# sumo_motor_5.net
KiCad netlist of a schematic drawn in EAGLE
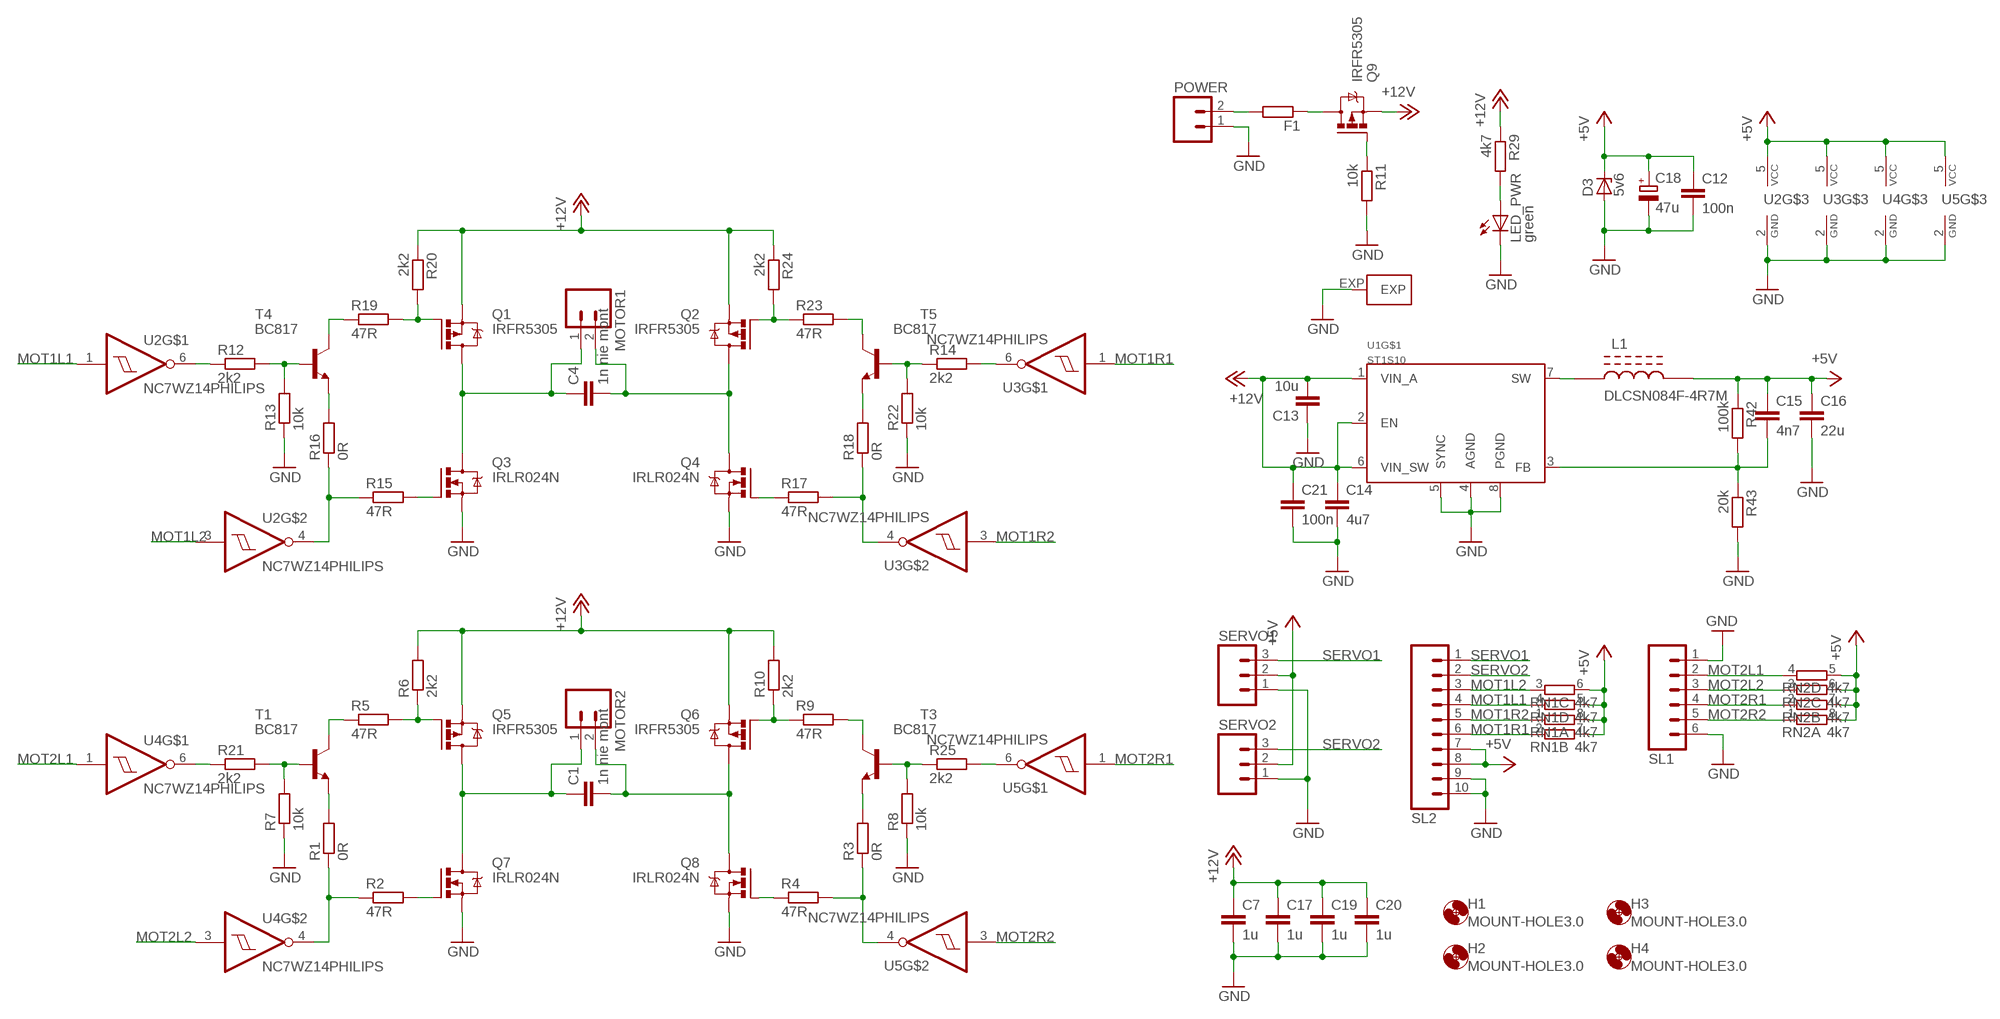
[diagram p0: schematic, sheet 1]

(export (version "E")
  (design (tool "Eeschema 10.0.6"))
  (components
    (comp (ref "C1")
      (value "1n nie mont")
      (footprint "eagle-import:C025-025X050")
      (libsource (lib "eagle-import") (part "C-EU025-025X050"))
    )
    (comp (ref "C4")
      (value "1n nie mont")
      (footprint "eagle-import:C025-025X050")
      (libsource (lib "eagle-import") (part "C-EU025-025X050"))
    )
    (comp (ref "C7")
      (value "1u")
      (footprint "eagle-import:C0805")
      (libsource (lib "eagle-import") (part "C-EUC0805"))
    )
    (comp (ref "C12")
      (value "100n")
      (footprint "eagle-import:C0805")
      (libsource (lib "eagle-import") (part "C-EUC0805"))
    )
    (comp (ref "C13")
      (value "10u")
      (footprint "eagle-import:C1206K")
      (libsource (lib "eagle-import") (part "C-EUC1206K"))
    )
    (comp (ref "C14")
      (value "4u7")
      (footprint "eagle-import:C0805")
      (libsource (lib "eagle-import") (part "C-EUC0805"))
    )
    (comp (ref "C15")
      (value "4n7")
      (footprint "eagle-import:C0805")
      (libsource (lib "eagle-import") (part "C-EUC0805"))
    )
    (comp (ref "C16")
      (value "22u")
      (footprint "eagle-import:C0805")
      (libsource (lib "eagle-import") (part "C-EUC0805"))
    )
    (comp (ref "C17")
      (value "1u")
      (footprint "eagle-import:C0805")
      (libsource (lib "eagle-import") (part "C-EUC0805"))
    )
    (comp (ref "C18")
      (value "47u")
      (footprint "eagle-import:SMC_B")
      (libsource (lib "eagle-import") (part "CPOL-EUSMCB"))
    )
    (comp (ref "C19")
      (value "1u")
      (footprint "eagle-import:C0805")
      (libsource (lib "eagle-import") (part "C-EUC0805"))
    )
    (comp (ref "C20")
      (value "1u")
      (footprint "eagle-import:C0805")
      (libsource (lib "eagle-import") (part "C-EUC0805"))
    )
    (comp (ref "C21")
      (value "100n")
      (footprint "eagle-import:C0805")
      (libsource (lib "eagle-import") (part "C-EUC0805"))
    )
    (comp (ref "D3")
      (value "5v6")
      (footprint "eagle-import:SMB")
      (libsource (lib "eagle-import") (part "ZENER-DIODESMB"))
    )
    (comp (ref "F1")
      (value "R-EU_VMTA55")
      (footprint "eagle-import:VMTA55")
      (libsource (lib "eagle-import") (part "R-EU_VMTA55"))
    )
    (comp (ref "H1")
      (value "MOUNT-HOLE3.0")
      (footprint "eagle-import:3,0")
      (libsource (lib "eagle-import") (part "MOUNT-HOLE3.0"))
    )
    (comp (ref "H2")
      (value "MOUNT-HOLE3.0")
      (footprint "eagle-import:3,0")
      (libsource (lib "eagle-import") (part "MOUNT-HOLE3.0"))
    )
    (comp (ref "H3")
      (value "MOUNT-HOLE3.0")
      (footprint "eagle-import:3,0")
      (libsource (lib "eagle-import") (part "MOUNT-HOLE3.0"))
    )
    (comp (ref "H4")
      (value "MOUNT-HOLE3.0")
      (footprint "eagle-import:3,0")
      (libsource (lib "eagle-import") (part "MOUNT-HOLE3.0"))
    )
    (comp (ref "L1")
      (value "DLCSN084F-4R7M")
      (footprint "eagle-import:CSN084F")
      (libsource (lib "eagle-import") (part "DLCSN084F"))
    )
    (comp (ref "LED_PWR")
      (value "green")
      (footprint "eagle-import:SML0805")
      (libsource (lib "eagle-import") (part "LEDSML0805"))
    )
    (comp (ref "MOTOR1")
      (value "M02")
      (footprint "eagle-import:02P")
      (libsource (lib "eagle-import") (part "M02"))
    )
    (comp (ref "MOTOR2")
      (value "M02")
      (footprint "eagle-import:02P")
      (libsource (lib "eagle-import") (part "M02"))
    )
    (comp (ref "POWER")
      (value "M02")
      (footprint "eagle-import:02P")
      (libsource (lib "eagle-import") (part "M02"))
    )
    (comp (ref "Q1")
      (value "IRFR5305")
      (footprint "eagle-import:D-PAK_TO252AA")
      (libsource (lib "eagle-import") (part "IRF?5305R"))
    )
    (comp (ref "Q2")
      (value "IRFR5305")
      (footprint "eagle-import:D-PAK_TO252AA")
      (libsource (lib "eagle-import") (part "IRF?5305R"))
    )
    (comp (ref "Q3")
      (value "IRLR024N")
      (footprint "eagle-import:D-PAK_TO252AA")
      (libsource (lib "eagle-import") (part "IRLR024N"))
    )
    (comp (ref "Q4")
      (value "IRLR024N")
      (footprint "eagle-import:D-PAK_TO252AA")
      (libsource (lib "eagle-import") (part "IRLR024N"))
    )
    (comp (ref "Q5")
      (value "IRFR5305")
      (footprint "eagle-import:D-PAK_TO252AA")
      (libsource (lib "eagle-import") (part "IRF?5305R"))
    )
    (comp (ref "Q6")
      (value "IRFR5305")
      (footprint "eagle-import:D-PAK_TO252AA")
      (libsource (lib "eagle-import") (part "IRF?5305R"))
    )
    (comp (ref "Q7")
      (value "IRLR024N")
      (footprint "eagle-import:D-PAK_TO252AA")
      (libsource (lib "eagle-import") (part "IRLR024N"))
    )
    (comp (ref "Q8")
      (value "IRLR024N")
      (footprint "eagle-import:D-PAK_TO252AA")
      (libsource (lib "eagle-import") (part "IRLR024N"))
    )
    (comp (ref "Q9")
      (value "IRFR5305")
      (footprint "eagle-import:D-PAK_TO252AA")
      (libsource (lib "eagle-import") (part "IRF?5305R"))
    )
    (comp (ref "R1")
      (value "0R")
      (footprint "eagle-import:R0603")
      (libsource (lib "eagle-import") (part "R-EU_R0603"))
    )
    (comp (ref "R2")
      (value "47R")
      (footprint "eagle-import:R0603")
      (libsource (lib "eagle-import") (part "R-EU_R0603"))
    )
    (comp (ref "R3")
      (value "0R")
      (footprint "eagle-import:R0603")
      (libsource (lib "eagle-import") (part "R-EU_R0603"))
    )
    (comp (ref "R4")
      (value "47R")
      (footprint "eagle-import:R0603")
      (libsource (lib "eagle-import") (part "R-EU_R0603"))
    )
    (comp (ref "R5")
      (value "47R")
      (footprint "eagle-import:R0603")
      (libsource (lib "eagle-import") (part "R-EU_R0603"))
    )
    (comp (ref "R6")
      (value "2k2")
      (footprint "eagle-import:R0603")
      (libsource (lib "eagle-import") (part "R-EU_R0603"))
    )
    (comp (ref "R7")
      (value "10k")
      (footprint "eagle-import:R0603")
      (libsource (lib "eagle-import") (part "R-EU_R0603"))
    )
    (comp (ref "R8")
      (value "10k")
      (footprint "eagle-import:R0603")
      (libsource (lib "eagle-import") (part "R-EU_R0603"))
    )
    (comp (ref "R9")
      (value "47R")
      (footprint "eagle-import:R0603")
      (libsource (lib "eagle-import") (part "R-EU_R0603"))
    )
    (comp (ref "R10")
      (value "2k2")
      (footprint "eagle-import:R0603")
      (libsource (lib "eagle-import") (part "R-EU_R0603"))
    )
    (comp (ref "R11")
      (value "10k")
      (footprint "eagle-import:R0603")
      (libsource (lib "eagle-import") (part "R-EU_R0603"))
    )
    (comp (ref "R12")
      (value "2k2")
      (footprint "eagle-import:R0603")
      (libsource (lib "eagle-import") (part "R-EU_R0603"))
    )
    (comp (ref "R13")
      (value "10k")
      (footprint "eagle-import:R0603")
      (libsource (lib "eagle-import") (part "R-EU_R0603"))
    )
    (comp (ref "R14")
      (value "2k2")
      (footprint "eagle-import:R0603")
      (libsource (lib "eagle-import") (part "R-EU_R0603"))
    )
    (comp (ref "R15")
      (value "47R")
      (footprint "eagle-import:R0603")
      (libsource (lib "eagle-import") (part "R-EU_R0603"))
    )
    (comp (ref "R16")
      (value "0R")
      (footprint "eagle-import:R0603")
      (libsource (lib "eagle-import") (part "R-EU_R0603"))
    )
    (comp (ref "R17")
      (value "47R")
      (footprint "eagle-import:R0603")
      (libsource (lib "eagle-import") (part "R-EU_R0603"))
    )
    (comp (ref "R18")
      (value "0R")
      (footprint "eagle-import:R0603")
      (libsource (lib "eagle-import") (part "R-EU_R0603"))
    )
    (comp (ref "R19")
      (value "47R")
      (footprint "eagle-import:R0603")
      (libsource (lib "eagle-import") (part "R-EU_R0603"))
    )
    (comp (ref "R20")
      (value "2k2")
      (footprint "eagle-import:R0603")
      (libsource (lib "eagle-import") (part "R-EU_R0603"))
    )
    (comp (ref "R21")
      (value "2k2")
      (footprint "eagle-import:R0603")
      (libsource (lib "eagle-import") (part "R-EU_R0603"))
    )
    (comp (ref "R22")
      (value "10k")
      (footprint "eagle-import:R0603")
      (libsource (lib "eagle-import") (part "R-EU_R0603"))
    )
    (comp (ref "R23")
      (value "47R")
      (footprint "eagle-import:R0603")
      (libsource (lib "eagle-import") (part "R-EU_R0603"))
    )
    (comp (ref "R24")
      (value "2k2")
      (footprint "eagle-import:R0603")
      (libsource (lib "eagle-import") (part "R-EU_R0603"))
    )
    (comp (ref "R25")
      (value "2k2")
      (footprint "eagle-import:R0603")
      (libsource (lib "eagle-import") (part "R-EU_R0603"))
    )
    (comp (ref "R29")
      (value "4k7")
      (footprint "eagle-import:R0603")
      (libsource (lib "eagle-import") (part "R-EU_R0603"))
    )
    (comp (ref "R42")
      (value "100k")
      (footprint "eagle-import:R0603")
      (libsource (lib "eagle-import") (part "R-EU_R0603"))
    )
    (comp (ref "R43")
      (value "20k")
      (footprint "eagle-import:R0603")
      (libsource (lib "eagle-import") (part "R-EU_R0603"))
    )
    (comp (ref "RN1")
      (value "4k7")
      (footprint "eagle-import:CAT16XXX")
      (libsource (lib "eagle-import") (part "CAT16XXXJ4CAT16"))
    )
    (comp (ref "RN2")
      (value "4k7")
      (footprint "eagle-import:CAT16XXX")
      (libsource (lib "eagle-import") (part "CAT16XXXJ4CAT16"))
    )
    (comp (ref "SERVO1")
      (value "M03")
      (footprint "eagle-import:03P")
      (libsource (lib "eagle-import") (part "M03"))
    )
    (comp (ref "SERVO2")
      (value "M03")
      (footprint "eagle-import:03P")
      (libsource (lib "eagle-import") (part "M03"))
    )
    (comp (ref "SL1")
      (value "M06")
      (footprint "eagle-import:06P")
      (fields (field (name "OC_FARNELL") "unknown") (field (name "OC_NEWARK") "unknown"))
      (libsource (lib "eagle-import") (part "M06"))
    )
    (comp (ref "SL2")
      (value "M10")
      (footprint "eagle-import:10P")
      (fields (field (name "OC_FARNELL") "unknown") (field (name "OC_NEWARK") "unknown"))
      (libsource (lib "eagle-import") (part "M10"))
    )
    (comp (ref "T1")
      (value "BC817")
      (footprint "eagle-import:SOT23-BEC")
      (libsource (lib "eagle-import") (part "-NPN-SOT23-BECBC817-16"))
    )
    (comp (ref "T3")
      (value "BC817")
      (footprint "eagle-import:SOT23-BEC")
      (libsource (lib "eagle-import") (part "-NPN-SOT23-BECBC817-16"))
    )
    (comp (ref "T4")
      (value "BC817")
      (footprint "eagle-import:SOT23-BEC")
      (libsource (lib "eagle-import") (part "-NPN-SOT23-BECBC817-16"))
    )
    (comp (ref "T5")
      (value "BC817")
      (footprint "eagle-import:SOT23-BEC")
      (libsource (lib "eagle-import") (part "-NPN-SOT23-BECBC817-16"))
    )
    (comp (ref "U1")
      (value "ST1S10")
      (footprint "eagle-import:HSOP8")
      (libsource (lib "eagle-import") (part "ST1S10"))
    )
    (comp (ref "U2")
      (value "NC7WZ14PHILIPS")
      (footprint "eagle-import:SOT363_PHILIPS")
      (libsource (lib "eagle-import") (part "NC7WZ14PHILIPS"))
    )
    (comp (ref "U3")
      (value "NC7WZ14PHILIPS")
      (footprint "eagle-import:SOT363_PHILIPS")
      (libsource (lib "eagle-import") (part "NC7WZ14PHILIPS"))
    )
    (comp (ref "U4")
      (value "NC7WZ14PHILIPS")
      (footprint "eagle-import:SOT363_PHILIPS")
      (libsource (lib "eagle-import") (part "NC7WZ14PHILIPS"))
    )
    (comp (ref "U5")
      (value "NC7WZ14PHILIPS")
      (footprint "eagle-import:SOT363_PHILIPS")
      (libsource (lib "eagle-import") (part "NC7WZ14PHILIPS"))
    )
  )
  (nets
    (net (code "1") (name "+5V") (class "Default")
      (node (ref "C12") (pin "1") (pinfunction "1_1") (pintype "passive"))
      (node (ref "C15") (pin "1") (pinfunction "1_1") (pintype "passive"))
      (node (ref "C16") (pin "1") (pinfunction "1_1") (pintype "passive"))
      (node (ref "C18") (pin "+") (pinfunction "+_+") (pintype "passive"))
      (node (ref "D3") (pin "C") (pinfunction "C_C") (pintype "passive"))
      (node (ref "L1") (pin "2") (pinfunction "2_2") (pintype "passive"))
      (node (ref "R42") (pin "1") (pinfunction "1_1") (pintype "passive"))
      (node (ref "RN1") (pin "5") (pinfunction "2_5") (pintype "passive"))
      (node (ref "RN1") (pin "6") (pinfunction "2_6") (pintype "passive"))
      (node (ref "RN1") (pin "7") (pinfunction "2_7") (pintype "passive"))
      (node (ref "RN1") (pin "8") (pinfunction "2_8") (pintype "passive"))
      (node (ref "RN2") (pin "5") (pinfunction "2_5") (pintype "passive"))
      (node (ref "RN2") (pin "6") (pinfunction "2_6") (pintype "passive"))
      (node (ref "RN2") (pin "7") (pinfunction "2_7") (pintype "passive"))
      (node (ref "RN2") (pin "8") (pinfunction "2_8") (pintype "passive"))
      (node (ref "SERVO1") (pin "2") (pinfunction "2_2") (pintype "passive"))
      (node (ref "SERVO2") (pin "2") (pinfunction "2_2") (pintype "passive"))
      (node (ref "SL2") (pin "7") (pinfunction "7_7") (pintype "passive"))
      (node (ref "SL2") (pin "8") (pinfunction "8_8") (pintype "passive"))
      (node (ref "U2") (pin "5") (pinfunction "VCC_5") (pintype "power_in"))
      (node (ref "U3") (pin "5") (pinfunction "VCC_5") (pintype "power_in"))
      (node (ref "U4") (pin "5") (pinfunction "VCC_5") (pintype "power_in"))
      (node (ref "U5") (pin "5") (pinfunction "VCC_5") (pintype "power_in"))
    )
    (net (code "2") (name "+12V") (class "Default")
      (node (ref "C13") (pin "2") (pinfunction "2_2") (pintype "passive"))
      (node (ref "C14") (pin "1") (pinfunction "1_1") (pintype "passive"))
      (node (ref "C17") (pin "1") (pinfunction "1_1") (pintype "passive"))
      (node (ref "C19") (pin "1") (pinfunction "1_1") (pintype "passive"))
      (node (ref "C20") (pin "1") (pinfunction "1_1") (pintype "passive"))
      (node (ref "C21") (pin "1") (pinfunction "1_1") (pintype "passive"))
      (node (ref "C7") (pin "1") (pinfunction "1_1") (pintype "passive"))
      (node (ref "Q1") (pin "3") (pinfunction "S_3") (pintype "passive"))
      (node (ref "Q2") (pin "3") (pinfunction "S_3") (pintype "passive"))
      (node (ref "Q5") (pin "3") (pinfunction "S_3") (pintype "passive"))
      (node (ref "Q6") (pin "3") (pinfunction "S_3") (pintype "passive"))
      (node (ref "Q9") (pin "3") (pinfunction "S_3") (pintype "passive"))
      (node (ref "R10") (pin "2") (pinfunction "2_2") (pintype "passive"))
      (node (ref "R20") (pin "1") (pinfunction "1_1") (pintype "passive"))
      (node (ref "R24") (pin "1") (pinfunction "1_1") (pintype "passive"))
      (node (ref "R29") (pin "1") (pinfunction "1_1") (pintype "passive"))
      (node (ref "R6") (pin "2") (pinfunction "2_2") (pintype "passive"))
      (node (ref "U1") (pin "1") (pinfunction "VIN_A_1") (pintype "power_in"))
      (node (ref "U1") (pin "2") (pinfunction "EN_2") (pintype "bidirectional"))
      (node (ref "U1") (pin "6") (pinfunction "VIN_SW_6") (pintype "power_in"))
    )
    (net (code "3") (name "/MOT1L1") (class "Default")
      (node (ref "RN1") (pin "4") (pinfunction "1_4") (pintype "passive"))
      (node (ref "SL2") (pin "4") (pinfunction "4_4") (pintype "passive"))
      (node (ref "U2") (pin "1") (pinfunction "I_1") (pintype "input"))
    )
    (net (code "4") (name "/MOT1L2") (class "Default")
      (node (ref "RN1") (pin "3") (pinfunction "1_3") (pintype "passive"))
      (node (ref "SL2") (pin "3") (pinfunction "3_3") (pintype "passive"))
      (node (ref "U2") (pin "3") (pinfunction "I_3") (pintype "input"))
    )
    (net (code "5") (name "/MOT1R1") (class "Default")
      (node (ref "RN1") (pin "2") (pinfunction "1_2") (pintype "passive"))
      (node (ref "SL2") (pin "6") (pinfunction "6_6") (pintype "passive"))
      (node (ref "U3") (pin "1") (pinfunction "I_1") (pintype "input"))
    )
    (net (code "6") (name "/MOT1R2") (class "Default")
      (node (ref "RN1") (pin "1") (pinfunction "1_1") (pintype "passive"))
      (node (ref "SL2") (pin "5") (pinfunction "5_5") (pintype "passive"))
      (node (ref "U3") (pin "3") (pinfunction "I_3") (pintype "input"))
    )
    (net (code "7") (name "/MOT2L1") (class "Default")
      (node (ref "RN2") (pin "4") (pinfunction "1_4") (pintype "passive"))
      (node (ref "SL1") (pin "2") (pinfunction "2_2") (pintype "passive"))
      (node (ref "U4") (pin "1") (pinfunction "I_1") (pintype "input"))
    )
    (net (code "8") (name "/MOT2L2") (class "Default")
      (node (ref "RN2") (pin "3") (pinfunction "1_3") (pintype "passive"))
      (node (ref "SL1") (pin "3") (pinfunction "3_3") (pintype "passive"))
      (node (ref "U4") (pin "3") (pinfunction "I_3") (pintype "input"))
    )
    (net (code "9") (name "/MOT2R1") (class "Default")
      (node (ref "RN2") (pin "2") (pinfunction "1_2") (pintype "passive"))
      (node (ref "SL1") (pin "4") (pinfunction "4_4") (pintype "passive"))
      (node (ref "U5") (pin "1") (pinfunction "I_1") (pintype "input"))
    )
    (net (code "10") (name "/MOT2R2") (class "Default")
      (node (ref "RN2") (pin "1") (pinfunction "1_1") (pintype "passive"))
      (node (ref "SL1") (pin "5") (pinfunction "5_5") (pintype "passive"))
      (node (ref "U5") (pin "3") (pinfunction "I_3") (pintype "input"))
    )
    (net (code "11") (name "/SERVO1") (class "Default")
      (node (ref "SERVO1") (pin "3") (pinfunction "3_3") (pintype "passive"))
      (node (ref "SL2") (pin "1") (pinfunction "1_1") (pintype "passive"))
    )
    (net (code "12") (name "/SERVO2") (class "Default")
      (node (ref "SERVO2") (pin "3") (pinfunction "3_3") (pintype "passive"))
      (node (ref "SL2") (pin "2") (pinfunction "2_2") (pintype "passive"))
    )
    (net (code "13") (name "GND") (class "Default")
      (node (ref "C12") (pin "2") (pinfunction "2_2") (pintype "passive"))
      (node (ref "C13") (pin "1") (pinfunction "1_1") (pintype "passive"))
      (node (ref "C14") (pin "2") (pinfunction "2_2") (pintype "passive"))
      (node (ref "C16") (pin "2") (pinfunction "2_2") (pintype "passive"))
      (node (ref "C17") (pin "2") (pinfunction "2_2") (pintype "passive"))
      (node (ref "C18") (pin "-") (pinfunction "-_-") (pintype "passive"))
      (node (ref "C19") (pin "2") (pinfunction "2_2") (pintype "passive"))
      (node (ref "C20") (pin "2") (pinfunction "2_2") (pintype "passive"))
      (node (ref "C21") (pin "2") (pinfunction "2_2") (pintype "passive"))
      (node (ref "C7") (pin "2") (pinfunction "2_2") (pintype "passive"))
      (node (ref "D3") (pin "A") (pinfunction "A_A") (pintype "passive"))
      (node (ref "LED_PWR") (pin "C") (pinfunction "C_C") (pintype "passive"))
      (node (ref "POWER") (pin "1") (pinfunction "1_1") (pintype "passive"))
      (node (ref "Q3") (pin "3") (pinfunction "S_3") (pintype "passive"))
      (node (ref "Q4") (pin "3") (pinfunction "S_3") (pintype "passive"))
      (node (ref "Q7") (pin "3") (pinfunction "S_3") (pintype "passive"))
      (node (ref "Q8") (pin "3") (pinfunction "S_3") (pintype "passive"))
      (node (ref "R11") (pin "2") (pinfunction "2_2") (pintype "passive"))
      (node (ref "R13") (pin "1") (pinfunction "1_1") (pintype "passive"))
      (node (ref "R22") (pin "1") (pinfunction "1_1") (pintype "passive"))
      (node (ref "R43") (pin "2") (pinfunction "2_2") (pintype "passive"))
      (node (ref "R7") (pin "1") (pinfunction "1_1") (pintype "passive"))
      (node (ref "R8") (pin "1") (pinfunction "1_1") (pintype "passive"))
      (node (ref "SERVO1") (pin "1") (pinfunction "1_1") (pintype "passive"))
      (node (ref "SERVO2") (pin "1") (pinfunction "1_1") (pintype "passive"))
      (node (ref "SL1") (pin "1") (pinfunction "1_1") (pintype "passive"))
      (node (ref "SL1") (pin "6") (pinfunction "6_6") (pintype "passive"))
      (node (ref "SL2") (pin "10") (pinfunction "10_10") (pintype "passive"))
      (node (ref "SL2") (pin "9") (pinfunction "9_9") (pintype "passive"))
      (node (ref "U1") (pin "4") (pinfunction "AGND_4") (pintype "power_in"))
      (node (ref "U1") (pin "5") (pinfunction "SYNC_5") (pintype "bidirectional"))
      (node (ref "U1") (pin "8") (pinfunction "PGND_8") (pintype "power_in"))
      (node (ref "U1") (pin "EXP") (pinfunction "EXP_EXP") (pintype "power_in"))
      (node (ref "U2") (pin "2") (pinfunction "GND_2") (pintype "power_in"))
      (node (ref "U3") (pin "2") (pinfunction "GND_2") (pintype "power_in"))
      (node (ref "U4") (pin "2") (pinfunction "GND_2") (pintype "power_in"))
      (node (ref "U5") (pin "2") (pinfunction "GND_2") (pintype "power_in"))
    )
    (net (code "14") (name "Net-(F1-Pad2)") (class "Default")
      (node (ref "F1") (pin "2") (pinfunction "2_2") (pintype "passive"))
      (node (ref "POWER") (pin "2") (pinfunction "2_2") (pintype "passive"))
    )
    (net (code "15") (name "Net-(LED_PWR-PadA)") (class "Default")
      (node (ref "LED_PWR") (pin "A") (pinfunction "A_A") (pintype "passive"))
      (node (ref "R29") (pin "2") (pinfunction "2_2") (pintype "passive"))
    )
    (net (code "16") (name "Net-(Q1-D)") (class "Default")
      (node (ref "C4") (pin "1") (pinfunction "1_1") (pintype "passive"))
      (node (ref "MOTOR1") (pin "1") (pinfunction "1_1") (pintype "passive"))
      (node (ref "Q1") (pin "4") (pinfunction "D_4") (pintype "passive"))
      (node (ref "Q3") (pin "4") (pinfunction "D_4") (pintype "passive"))
    )
    (net (code "17") (name "Net-(Q1-G)") (class "Default")
      (node (ref "Q1") (pin "1") (pinfunction "G_1") (pintype "passive"))
      (node (ref "R19") (pin "2") (pinfunction "2_2") (pintype "passive"))
      (node (ref "R20") (pin "2") (pinfunction "2_2") (pintype "passive"))
    )
    (net (code "18") (name "Net-(Q2-D)") (class "Default")
      (node (ref "C4") (pin "2") (pinfunction "2_2") (pintype "passive"))
      (node (ref "MOTOR1") (pin "2") (pinfunction "2_2") (pintype "passive"))
      (node (ref "Q2") (pin "4") (pinfunction "D_4") (pintype "passive"))
      (node (ref "Q4") (pin "4") (pinfunction "D_4") (pintype "passive"))
    )
    (net (code "19") (name "Net-(Q2-G)") (class "Default")
      (node (ref "Q2") (pin "1") (pinfunction "G_1") (pintype "passive"))
      (node (ref "R23") (pin "1") (pinfunction "1_1") (pintype "passive"))
      (node (ref "R24") (pin "2") (pinfunction "2_2") (pintype "passive"))
    )
    (net (code "20") (name "Net-(Q3-G)") (class "Default")
      (node (ref "Q3") (pin "1") (pinfunction "G_1") (pintype "passive"))
      (node (ref "R15") (pin "2") (pinfunction "2_2") (pintype "passive"))
    )
    (net (code "21") (name "Net-(Q4-G)") (class "Default")
      (node (ref "Q4") (pin "1") (pinfunction "G_1") (pintype "passive"))
      (node (ref "R17") (pin "1") (pinfunction "1_1") (pintype "passive"))
    )
    (net (code "22") (name "Net-(Q5-D)") (class "Default")
      (node (ref "C1") (pin "1") (pinfunction "1_1") (pintype "passive"))
      (node (ref "MOTOR2") (pin "1") (pinfunction "1_1") (pintype "passive"))
      (node (ref "Q5") (pin "4") (pinfunction "D_4") (pintype "passive"))
      (node (ref "Q7") (pin "4") (pinfunction "D_4") (pintype "passive"))
    )
    (net (code "23") (name "Net-(Q5-G)") (class "Default")
      (node (ref "Q5") (pin "1") (pinfunction "G_1") (pintype "passive"))
      (node (ref "R5") (pin "2") (pinfunction "2_2") (pintype "passive"))
      (node (ref "R6") (pin "1") (pinfunction "1_1") (pintype "passive"))
    )
    (net (code "24") (name "Net-(Q6-D)") (class "Default")
      (node (ref "C1") (pin "2") (pinfunction "2_2") (pintype "passive"))
      (node (ref "MOTOR2") (pin "2") (pinfunction "2_2") (pintype "passive"))
      (node (ref "Q6") (pin "4") (pinfunction "D_4") (pintype "passive"))
      (node (ref "Q8") (pin "4") (pinfunction "D_4") (pintype "passive"))
    )
    (net (code "25") (name "Net-(Q6-G)") (class "Default")
      (node (ref "Q6") (pin "1") (pinfunction "G_1") (pintype "passive"))
      (node (ref "R10") (pin "1") (pinfunction "1_1") (pintype "passive"))
      (node (ref "R9") (pin "1") (pinfunction "1_1") (pintype "passive"))
    )
    (net (code "26") (name "Net-(Q7-G)") (class "Default")
      (node (ref "Q7") (pin "1") (pinfunction "G_1") (pintype "passive"))
      (node (ref "R2") (pin "2") (pinfunction "2_2") (pintype "passive"))
    )
    (net (code "27") (name "Net-(Q8-G)") (class "Default")
      (node (ref "Q8") (pin "1") (pinfunction "G_1") (pintype "passive"))
      (node (ref "R4") (pin "1") (pinfunction "1_1") (pintype "passive"))
    )
    (net (code "28") (name "Net-(Q9-D)") (class "Default")
      (node (ref "F1") (pin "1") (pinfunction "1_1") (pintype "passive"))
      (node (ref "Q9") (pin "4") (pinfunction "D_4") (pintype "passive"))
    )
    (net (code "29") (name "Net-(Q9-G)") (class "Default")
      (node (ref "Q9") (pin "1") (pinfunction "G_1") (pintype "passive"))
      (node (ref "R11") (pin "1") (pinfunction "1_1") (pintype "passive"))
    )
    (net (code "30") (name "Net-(R1-Pad2)") (class "Default")
      (node (ref "R1") (pin "2") (pinfunction "2_2") (pintype "passive"))
      (node (ref "T1") (pin "E") (pinfunction "E_E") (pintype "passive"))
    )
    (net (code "31") (name "Net-(R3-Pad2)") (class "Default")
      (node (ref "R3") (pin "2") (pinfunction "2_2") (pintype "passive"))
      (node (ref "T3") (pin "E") (pinfunction "E_E") (pintype "passive"))
    )
    (net (code "32") (name "Net-(R5-Pad1)") (class "Default")
      (node (ref "R5") (pin "1") (pinfunction "1_1") (pintype "passive"))
      (node (ref "T1") (pin "C") (pinfunction "C_C") (pintype "passive"))
    )
    (net (code "33") (name "Net-(R9-Pad2)") (class "Default")
      (node (ref "R9") (pin "2") (pinfunction "2_2") (pintype "passive"))
      (node (ref "T3") (pin "C") (pinfunction "C_C") (pintype "passive"))
    )
    (net (code "34") (name "Net-(R12-Pad2)") (class "Default")
      (node (ref "R12") (pin "2") (pinfunction "2_2") (pintype "passive"))
      (node (ref "R13") (pin "2") (pinfunction "2_2") (pintype "passive"))
      (node (ref "T4") (pin "B") (pinfunction "B_B") (pintype "passive"))
    )
    (net (code "35") (name "Net-(R14-Pad1)") (class "Default")
      (node (ref "R14") (pin "1") (pinfunction "1_1") (pintype "passive"))
      (node (ref "R22") (pin "2") (pinfunction "2_2") (pintype "passive"))
      (node (ref "T5") (pin "B") (pinfunction "B_B") (pintype "passive"))
    )
    (net (code "36") (name "Net-(R16-Pad2)") (class "Default")
      (node (ref "R16") (pin "2") (pinfunction "2_2") (pintype "passive"))
      (node (ref "T4") (pin "E") (pinfunction "E_E") (pintype "passive"))
    )
    (net (code "37") (name "Net-(R18-Pad2)") (class "Default")
      (node (ref "R18") (pin "2") (pinfunction "2_2") (pintype "passive"))
      (node (ref "T5") (pin "E") (pinfunction "E_E") (pintype "passive"))
    )
    (net (code "38") (name "Net-(R19-Pad1)") (class "Default")
      (node (ref "R19") (pin "1") (pinfunction "1_1") (pintype "passive"))
      (node (ref "T4") (pin "C") (pinfunction "C_C") (pintype "passive"))
    )
    (net (code "39") (name "Net-(R21-Pad2)") (class "Default")
      (node (ref "R21") (pin "2") (pinfunction "2_2") (pintype "passive"))
      (node (ref "R7") (pin "2") (pinfunction "2_2") (pintype "passive"))
      (node (ref "T1") (pin "B") (pinfunction "B_B") (pintype "passive"))
    )
    (net (code "40") (name "Net-(R23-Pad2)") (class "Default")
      (node (ref "R23") (pin "2") (pinfunction "2_2") (pintype "passive"))
      (node (ref "T5") (pin "C") (pinfunction "C_C") (pintype "passive"))
    )
    (net (code "41") (name "Net-(R25-Pad1)") (class "Default")
      (node (ref "R25") (pin "1") (pinfunction "1_1") (pintype "passive"))
      (node (ref "R8") (pin "2") (pinfunction "2_2") (pintype "passive"))
      (node (ref "T3") (pin "B") (pinfunction "B_B") (pintype "passive"))
    )
    (net (code "42") (name "Net-(U1A-FB)") (class "Default")
      (node (ref "C15") (pin "2") (pinfunction "2_2") (pintype "passive"))
      (node (ref "R42") (pin "2") (pinfunction "2_2") (pintype "passive"))
      (node (ref "R43") (pin "1") (pinfunction "1_1") (pintype "passive"))
      (node (ref "U1") (pin "3") (pinfunction "FB_3") (pintype "bidirectional"))
    )
    (net (code "43") (name "Net-(U1A-SW)") (class "Default")
      (node (ref "L1") (pin "1") (pinfunction "1_1") (pintype "passive"))
      (node (ref "U1") (pin "7") (pinfunction "SW_7") (pintype "bidirectional"))
    )
    (net (code "44") (name "Net-(U2A-O)") (class "Default")
      (node (ref "R12") (pin "1") (pinfunction "1_1") (pintype "passive"))
      (node (ref "U2") (pin "6") (pinfunction "O_6") (pintype "output"))
    )
    (net (code "45") (name "Net-(U2B-O)") (class "Default")
      (node (ref "R15") (pin "1") (pinfunction "1_1") (pintype "passive"))
      (node (ref "R16") (pin "1") (pinfunction "1_1") (pintype "passive"))
      (node (ref "U2") (pin "4") (pinfunction "O_4") (pintype "output"))
    )
    (net (code "46") (name "Net-(U3A-O)") (class "Default")
      (node (ref "R14") (pin "2") (pinfunction "2_2") (pintype "passive"))
      (node (ref "U3") (pin "6") (pinfunction "O_6") (pintype "output"))
    )
    (net (code "47") (name "Net-(U3B-O)") (class "Default")
      (node (ref "R17") (pin "2") (pinfunction "2_2") (pintype "passive"))
      (node (ref "R18") (pin "1") (pinfunction "1_1") (pintype "passive"))
      (node (ref "U3") (pin "4") (pinfunction "O_4") (pintype "output"))
    )
    (net (code "48") (name "Net-(U4A-O)") (class "Default")
      (node (ref "R21") (pin "1") (pinfunction "1_1") (pintype "passive"))
      (node (ref "U4") (pin "6") (pinfunction "O_6") (pintype "output"))
    )
    (net (code "49") (name "Net-(U4B-O)") (class "Default")
      (node (ref "R1") (pin "1") (pinfunction "1_1") (pintype "passive"))
      (node (ref "R2") (pin "1") (pinfunction "1_1") (pintype "passive"))
      (node (ref "U4") (pin "4") (pinfunction "O_4") (pintype "output"))
    )
    (net (code "50") (name "Net-(U5A-O)") (class "Default")
      (node (ref "R25") (pin "2") (pinfunction "2_2") (pintype "passive"))
      (node (ref "U5") (pin "6") (pinfunction "O_6") (pintype "output"))
    )
    (net (code "51") (name "Net-(U5B-O)") (class "Default")
      (node (ref "R3") (pin "1") (pinfunction "1_1") (pintype "passive"))
      (node (ref "R4") (pin "2") (pinfunction "2_2") (pintype "passive"))
      (node (ref "U5") (pin "4") (pinfunction "O_4") (pintype "output"))
    )
  )
)
